# Isolated_Motor_Driver.net
KiCad netlist of a schematic drawn in EAGLE
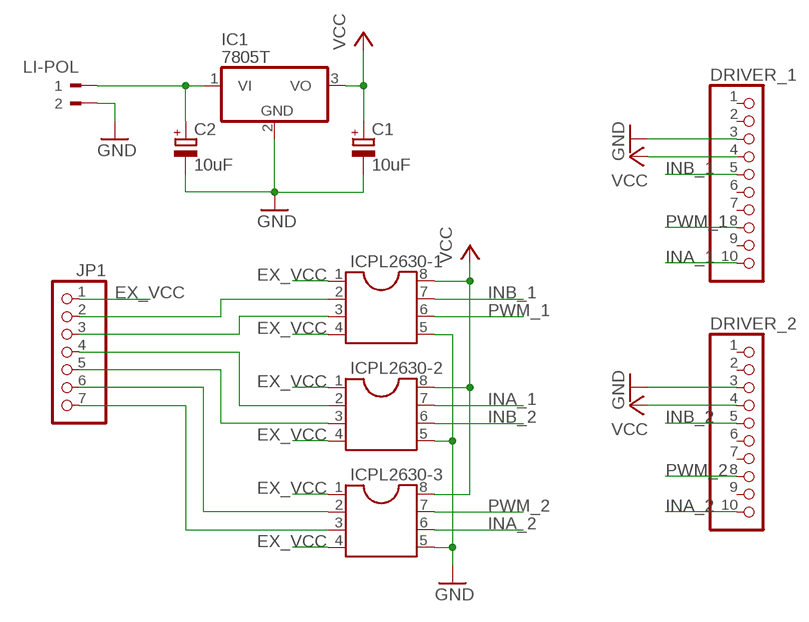
[diagram p0: schematic, sheet 1]

(export (version "E")
  (design (tool "Eeschema 10.0.6"))
  (components
    (comp (ref "C1")
      (value "10uF")
      (footprint "eagle-import:E5-5")
      (libsource (lib "eagle-import") (part "CPOL-EUE5-5"))
    )
    (comp (ref "C2")
      (value "10uF")
      (footprint "eagle-import:E5-5")
      (libsource (lib "eagle-import") (part "CPOL-EUE5-5"))
    )
    (comp (ref "DRIVER_1")
      (value "PINHD-1X10")
      (footprint "eagle-import:1X10")
      (libsource (lib "eagle-import") (part "PINHD-1X10"))
    )
    (comp (ref "DRIVER_2")
      (value "PINHD-1X10")
      (footprint "eagle-import:1X10")
      (libsource (lib "eagle-import") (part "PINHD-1X10"))
    )
    (comp (ref "IC1")
      (value "7805T")
      (footprint "eagle-import:TO220H")
      (libsource (lib "eagle-import") (part "78T05"))
    )
    (comp (ref "ICPL2630-1")
      (value "DIL8S")
      (footprint "eagle-import:SOCKET-08")
      (libsource (lib "eagle-import") (part "DIL8S"))
    )
    (comp (ref "ICPL2630-2")
      (value "DIL8S")
      (footprint "eagle-import:SOCKET-08")
      (libsource (lib "eagle-import") (part "DIL8S"))
    )
    (comp (ref "ICPL2630-3")
      (value "DIL8S")
      (footprint "eagle-import:SOCKET-08")
      (libsource (lib "eagle-import") (part "DIL8S"))
    )
    (comp (ref "JP1")
      (value "PINHD-1X7")
      (footprint "eagle-import:1X07")
      (libsource (lib "eagle-import") (part "PINHD-1X7"))
    )
    (comp (ref "LI-POL")
      (value "90-2")
      (footprint "eagle-import:90-2")
      (libsource (lib "eagle-import") (part "90-2"))
    )
  )
  (nets
    (net (code "1") (name "/EX_VCC") (class "Default")
      (node (ref "ICPL2630-1") (pin "1") (pinfunction "1_1") (pintype "passive"))
      (node (ref "ICPL2630-1") (pin "4") (pinfunction "4_4") (pintype "passive"))
      (node (ref "ICPL2630-2") (pin "1") (pinfunction "1_1") (pintype "passive"))
      (node (ref "ICPL2630-2") (pin "4") (pinfunction "4_4") (pintype "passive"))
      (node (ref "ICPL2630-3") (pin "1") (pinfunction "1_1") (pintype "passive"))
      (node (ref "ICPL2630-3") (pin "4") (pinfunction "4_4") (pintype "passive"))
      (node (ref "JP1") (pin "1") (pinfunction "1_1") (pintype "passive"))
    )
    (net (code "2") (name "/INA_1") (class "Default")
      (node (ref "DRIVER_1") (pin "10") (pinfunction "10_10") (pintype "passive"))
      (node (ref "ICPL2630-2") (pin "7") (pinfunction "7_7") (pintype "passive"))
    )
    (net (code "3") (name "/INA_2") (class "Default")
      (node (ref "DRIVER_2") (pin "10") (pinfunction "10_10") (pintype "passive"))
      (node (ref "ICPL2630-3") (pin "6") (pinfunction "6_6") (pintype "passive"))
    )
    (net (code "4") (name "/INB_1") (class "Default")
      (node (ref "DRIVER_1") (pin "5") (pinfunction "5_5") (pintype "passive"))
      (node (ref "ICPL2630-1") (pin "7") (pinfunction "7_7") (pintype "passive"))
    )
    (net (code "5") (name "/INB_2") (class "Default")
      (node (ref "DRIVER_2") (pin "5") (pinfunction "5_5") (pintype "passive"))
      (node (ref "ICPL2630-2") (pin "6") (pinfunction "6_6") (pintype "passive"))
    )
    (net (code "6") (name "/PWM_1") (class "Default")
      (node (ref "DRIVER_1") (pin "8") (pinfunction "8_8") (pintype "passive"))
      (node (ref "ICPL2630-1") (pin "6") (pinfunction "6_6") (pintype "passive"))
    )
    (net (code "7") (name "/PWM_2") (class "Default")
      (node (ref "DRIVER_2") (pin "8") (pinfunction "8_8") (pintype "passive"))
      (node (ref "ICPL2630-3") (pin "7") (pinfunction "7_7") (pintype "passive"))
    )
    (net (code "8") (name "GND") (class "Default")
      (node (ref "C1") (pin "-") (pinfunction "-_-") (pintype "passive"))
      (node (ref "C2") (pin "-") (pinfunction "-_-") (pintype "passive"))
      (node (ref "DRIVER_1") (pin "3") (pinfunction "3_3") (pintype "passive"))
      (node (ref "DRIVER_2") (pin "3") (pinfunction "3_3") (pintype "passive"))
      (node (ref "IC1") (pin "2") (pinfunction "GND_2") (pintype "passive"))
      (node (ref "ICPL2630-1") (pin "5") (pinfunction "5_5") (pintype "passive"))
      (node (ref "ICPL2630-2") (pin "5") (pinfunction "5_5") (pintype "passive"))
      (node (ref "ICPL2630-3") (pin "5") (pinfunction "5_5") (pintype "passive"))
      (node (ref "LI-POL") (pin "2") (pinfunction "2_2") (pintype "passive"))
    )
    (net (code "9") (name "Net-(IC1-VI)") (class "Default")
      (node (ref "C2") (pin "+") (pinfunction "+_+") (pintype "passive"))
      (node (ref "IC1") (pin "1") (pinfunction "VI_1") (pintype "input"))
      (node (ref "LI-POL") (pin "1") (pinfunction "1_1") (pintype "passive"))
    )
    (net (code "10") (name "Net-(ICPL2630-1-Pad2)") (class "Default")
      (node (ref "ICPL2630-1") (pin "2") (pinfunction "2_2") (pintype "passive"))
      (node (ref "JP1") (pin "2") (pinfunction "2_2") (pintype "passive"))
    )
    (net (code "11") (name "Net-(ICPL2630-1-Pad3)") (class "Default")
      (node (ref "ICPL2630-1") (pin "3") (pinfunction "3_3") (pintype "passive"))
      (node (ref "JP1") (pin "3") (pinfunction "3_3") (pintype "passive"))
    )
    (net (code "12") (name "Net-(ICPL2630-2-Pad2)") (class "Default")
      (node (ref "ICPL2630-2") (pin "2") (pinfunction "2_2") (pintype "passive"))
      (node (ref "JP1") (pin "4") (pinfunction "4_4") (pintype "passive"))
    )
    (net (code "13") (name "Net-(ICPL2630-2-Pad3)") (class "Default")
      (node (ref "ICPL2630-2") (pin "3") (pinfunction "3_3") (pintype "passive"))
      (node (ref "JP1") (pin "5") (pinfunction "5_5") (pintype "passive"))
    )
    (net (code "14") (name "Net-(ICPL2630-3-Pad2)") (class "Default")
      (node (ref "ICPL2630-3") (pin "2") (pinfunction "2_2") (pintype "passive"))
      (node (ref "JP1") (pin "6") (pinfunction "6_6") (pintype "passive"))
    )
    (net (code "15") (name "Net-(ICPL2630-3-Pad3)") (class "Default")
      (node (ref "ICPL2630-3") (pin "3") (pinfunction "3_3") (pintype "passive"))
      (node (ref "JP1") (pin "7") (pinfunction "7_7") (pintype "passive"))
    )
    (net (code "16") (name "VCC") (class "Default")
      (node (ref "C1") (pin "+") (pinfunction "+_+") (pintype "passive"))
      (node (ref "DRIVER_1") (pin "4") (pinfunction "4_4") (pintype "passive"))
      (node (ref "DRIVER_2") (pin "4") (pinfunction "4_4") (pintype "passive"))
      (node (ref "IC1") (pin "3") (pinfunction "VO_3") (pintype "passive"))
      (node (ref "ICPL2630-1") (pin "8") (pinfunction "8_8") (pintype "passive"))
      (node (ref "ICPL2630-2") (pin "8") (pinfunction "8_8") (pintype "passive"))
      (node (ref "ICPL2630-3") (pin "8") (pinfunction "8_8") (pintype "passive"))
    )
    (net (code "17") (name "unconnected-(DRIVER_1-Pad1)") (class "Default")
      (node (ref "DRIVER_1") (pin "1") (pinfunction "1_1") (pintype "passive"))
    )
    (net (code "18") (name "unconnected-(DRIVER_1-Pad2)") (class "Default")
      (node (ref "DRIVER_1") (pin "2") (pinfunction "2_2") (pintype "passive"))
    )
    (net (code "19") (name "unconnected-(DRIVER_1-Pad6)") (class "Default")
      (node (ref "DRIVER_1") (pin "6") (pinfunction "6_6") (pintype "passive"))
    )
    (net (code "20") (name "unconnected-(DRIVER_1-Pad7)") (class "Default")
      (node (ref "DRIVER_1") (pin "7") (pinfunction "7_7") (pintype "passive"))
    )
    (net (code "21") (name "unconnected-(DRIVER_1-Pad9)") (class "Default")
      (node (ref "DRIVER_1") (pin "9") (pinfunction "9_9") (pintype "passive"))
    )
    (net (code "22") (name "unconnected-(DRIVER_2-Pad1)") (class "Default")
      (node (ref "DRIVER_2") (pin "1") (pinfunction "1_1") (pintype "passive"))
    )
    (net (code "23") (name "unconnected-(DRIVER_2-Pad2)") (class "Default")
      (node (ref "DRIVER_2") (pin "2") (pinfunction "2_2") (pintype "passive"))
    )
    (net (code "24") (name "unconnected-(DRIVER_2-Pad6)") (class "Default")
      (node (ref "DRIVER_2") (pin "6") (pinfunction "6_6") (pintype "passive"))
    )
    (net (code "25") (name "unconnected-(DRIVER_2-Pad7)") (class "Default")
      (node (ref "DRIVER_2") (pin "7") (pinfunction "7_7") (pintype "passive"))
    )
    (net (code "26") (name "unconnected-(DRIVER_2-Pad9)") (class "Default")
      (node (ref "DRIVER_2") (pin "9") (pinfunction "9_9") (pintype "passive"))
    )
  )
)
